# USB_Hub.net
KiCad netlist of a schematic drawn in EAGLE
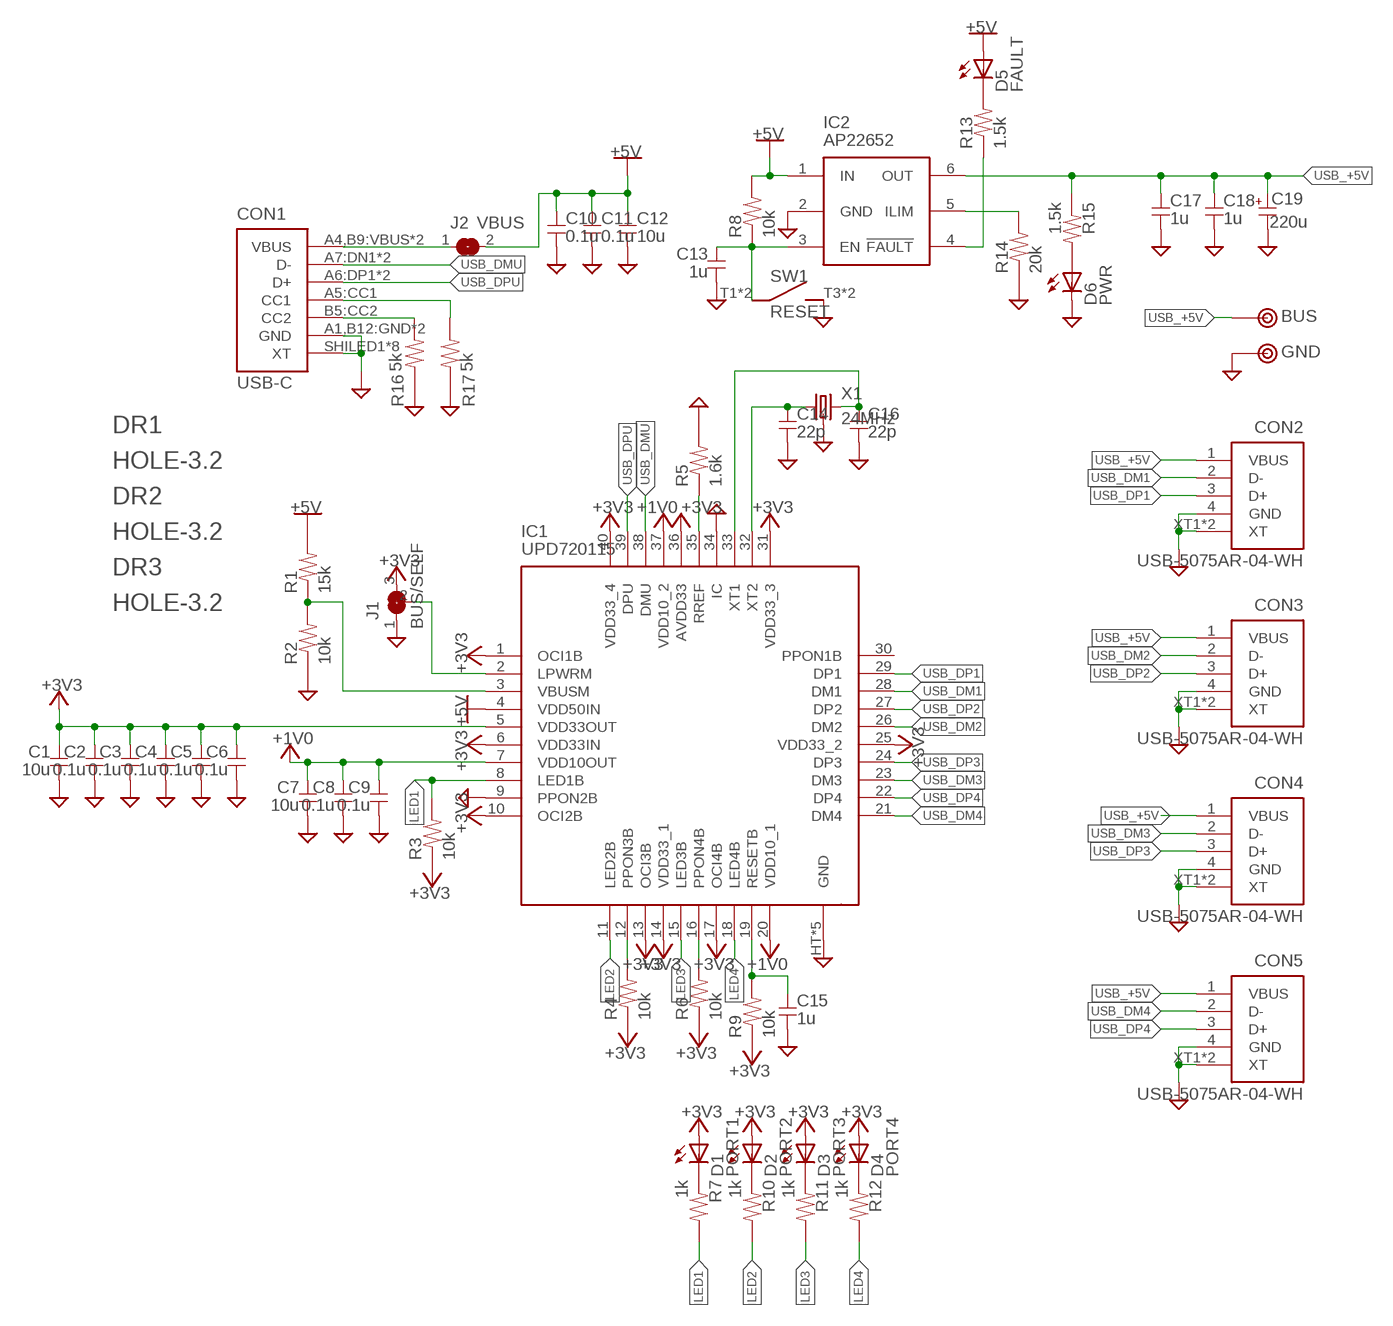
[diagram p0: schematic, sheet 1]

(export (version "E")
  (design (tool "Eeschema 10.0.6"))
  (components
    (comp (ref "C1")
      (value "10u")
      (footprint "eagle-import:1608")
      (libsource (lib "eagle-import") (part "C-1608"))
    )
    (comp (ref "C2")
      (value "0.1u")
      (footprint "eagle-import:1608")
      (libsource (lib "eagle-import") (part "C-1608"))
    )
    (comp (ref "C3")
      (value "0.1u")
      (footprint "eagle-import:1608")
      (libsource (lib "eagle-import") (part "C-1608"))
    )
    (comp (ref "C4")
      (value "0.1u")
      (footprint "eagle-import:1608")
      (libsource (lib "eagle-import") (part "C-1608"))
    )
    (comp (ref "C5")
      (value "0.1u")
      (footprint "eagle-import:1608")
      (libsource (lib "eagle-import") (part "C-1608"))
    )
    (comp (ref "C6")
      (value "0.1u")
      (footprint "eagle-import:1608")
      (libsource (lib "eagle-import") (part "C-1608"))
    )
    (comp (ref "C7")
      (value "10u")
      (footprint "eagle-import:1608")
      (libsource (lib "eagle-import") (part "C-1608"))
    )
    (comp (ref "C8")
      (value "0.1u")
      (footprint "eagle-import:1608")
      (libsource (lib "eagle-import") (part "C-1608"))
    )
    (comp (ref "C9")
      (value "0.1u")
      (footprint "eagle-import:1608")
      (libsource (lib "eagle-import") (part "C-1608"))
    )
    (comp (ref "C10")
      (value "0.1u")
      (footprint "eagle-import:1608")
      (libsource (lib "eagle-import") (part "C-1608"))
    )
    (comp (ref "C11")
      (value "0.1u")
      (footprint "eagle-import:1608")
      (libsource (lib "eagle-import") (part "C-1608"))
    )
    (comp (ref "C12")
      (value "10u")
      (footprint "eagle-import:2012")
      (libsource (lib "eagle-import") (part "C-2012"))
    )
    (comp (ref "C13")
      (value "1u")
      (footprint "eagle-import:1608")
      (libsource (lib "eagle-import") (part "C-1608"))
    )
    (comp (ref "C14")
      (value "22p")
      (footprint "eagle-import:1608")
      (libsource (lib "eagle-import") (part "C-1608"))
    )
    (comp (ref "C15")
      (value "1u")
      (footprint "eagle-import:1608")
      (libsource (lib "eagle-import") (part "C-1608"))
    )
    (comp (ref "C16")
      (value "22p")
      (footprint "eagle-import:1608")
      (libsource (lib "eagle-import") (part "C-1608"))
    )
    (comp (ref "C17")
      (value "1u")
      (footprint "eagle-import:1608")
      (libsource (lib "eagle-import") (part "C-1608"))
    )
    (comp (ref "C18")
      (value "1u")
      (footprint "eagle-import:1608")
      (libsource (lib "eagle-import") (part "C-1608"))
    )
    (comp (ref "C19")
      (value "220u")
      (footprint "eagle-import:E2.5-6.5")
      (libsource (lib "eagle-import") (part "CPOLE2.5-6.5"))
    )
    (comp (ref "CON1")
      (value "USB-C")
      (footprint "eagle-import:5077CR-16-SMC2-BK-TR")
      (libsource (lib "eagle-import") (part "USB-C"))
    )
    (comp (ref "CON2")
      (value "USB-5075AR-04-WH")
      (footprint "eagle-import:5075AR-04-WH")
      (libsource (lib "eagle-import") (part "USB-5075AR-04-WH"))
    )
    (comp (ref "CON3")
      (value "USB-5075AR-04-WH")
      (footprint "eagle-import:5075AR-04-WH")
      (libsource (lib "eagle-import") (part "USB-5075AR-04-WH"))
    )
    (comp (ref "CON4")
      (value "USB-5075AR-04-WH")
      (footprint "eagle-import:5075AR-04-WH")
      (libsource (lib "eagle-import") (part "USB-5075AR-04-WH"))
    )
    (comp (ref "CON5")
      (value "USB-5075AR-04-WH")
      (footprint "eagle-import:5075AR-04-WH")
      (libsource (lib "eagle-import") (part "USB-5075AR-04-WH"))
    )
    (comp (ref "D1")
      (value "PORT1")
      (footprint "eagle-import:LED2.5")
      (libsource (lib "eagle-import") (part "LED-2.5"))
    )
    (comp (ref "D2")
      (value "PORT2")
      (footprint "eagle-import:LED2.5")
      (libsource (lib "eagle-import") (part "LED-2.5"))
    )
    (comp (ref "D3")
      (value "PORT3")
      (footprint "eagle-import:LED2.5")
      (libsource (lib "eagle-import") (part "LED-2.5"))
    )
    (comp (ref "D4")
      (value "PORT4")
      (footprint "eagle-import:LED2.5")
      (libsource (lib "eagle-import") (part "LED-2.5"))
    )
    (comp (ref "D5")
      (value "FAULT")
      (footprint "eagle-import:D1608")
      (libsource (lib "eagle-import") (part "LED-SMD1608"))
    )
    (comp (ref "D6")
      (value "PWR")
      (footprint "eagle-import:D1608")
      (libsource (lib "eagle-import") (part "LED-SMD1608"))
    )
    (comp (ref "DR1")
      (value "HOLE-3.2")
      (footprint "eagle-import:HOLE_3.2")
      (libsource (lib "eagle-import") (part "HOLE-3.2"))
    )
    (comp (ref "DR2")
      (value "HOLE-3.2")
      (footprint "eagle-import:HOLE_3.2")
      (libsource (lib "eagle-import") (part "HOLE-3.2"))
    )
    (comp (ref "DR3")
      (value "HOLE-3.2")
      (footprint "eagle-import:HOLE_3.2")
      (libsource (lib "eagle-import") (part "HOLE-3.2"))
    )
    (comp (ref "IC1")
      (value "UPD720115")
      (footprint "eagle-import:QFN40HT")
      (libsource (lib "eagle-import") (part "UPD720115"))
    )
    (comp (ref "IC2")
      (value "AP22652")
      (footprint "eagle-import:SOT23-6")
      (libsource (lib "eagle-import") (part "AP22652"))
    )
    (comp (ref "J1")
      (value "BUS/SELF")
      (footprint "eagle-import:1608-3-J")
      (libsource (lib "eagle-import") (part "SJ-3-1608"))
    )
    (comp (ref "J2")
      (value "VBUS")
      (footprint "eagle-import:1608-J")
      (libsource (lib "eagle-import") (part "SJ-1608"))
    )
    (comp (ref "R1")
      (value "15k")
      (footprint "eagle-import:1608")
      (libsource (lib "eagle-import") (part "R-1608"))
    )
    (comp (ref "R2")
      (value "10k")
      (footprint "eagle-import:1608")
      (libsource (lib "eagle-import") (part "R-1608"))
    )
    (comp (ref "R3")
      (value "10k")
      (footprint "eagle-import:1608")
      (libsource (lib "eagle-import") (part "R-1608"))
    )
    (comp (ref "R4")
      (value "10k")
      (footprint "eagle-import:1608")
      (libsource (lib "eagle-import") (part "R-1608"))
    )
    (comp (ref "R5")
      (value "1.6k")
      (footprint "eagle-import:1608")
      (libsource (lib "eagle-import") (part "R-1608"))
    )
    (comp (ref "R6")
      (value "10k")
      (footprint "eagle-import:1608")
      (libsource (lib "eagle-import") (part "R-1608"))
    )
    (comp (ref "R7")
      (value "1k")
      (footprint "eagle-import:1608")
      (libsource (lib "eagle-import") (part "R-1608"))
    )
    (comp (ref "R8")
      (value "10k")
      (footprint "eagle-import:1608")
      (libsource (lib "eagle-import") (part "R-1608"))
    )
    (comp (ref "R9")
      (value "10k")
      (footprint "eagle-import:1608")
      (libsource (lib "eagle-import") (part "R-1608"))
    )
    (comp (ref "R10")
      (value "1k")
      (footprint "eagle-import:1608")
      (libsource (lib "eagle-import") (part "R-1608"))
    )
    (comp (ref "R11")
      (value "1k")
      (footprint "eagle-import:1608")
      (libsource (lib "eagle-import") (part "R-1608"))
    )
    (comp (ref "R12")
      (value "1k")
      (footprint "eagle-import:1608")
      (libsource (lib "eagle-import") (part "R-1608"))
    )
    (comp (ref "R13")
      (value "1.5k")
      (footprint "eagle-import:1608")
      (libsource (lib "eagle-import") (part "R-1608"))
    )
    (comp (ref "R14")
      (value "20k")
      (footprint "eagle-import:1608")
      (libsource (lib "eagle-import") (part "R-1608"))
    )
    (comp (ref "R15")
      (value "1.5k")
      (footprint "eagle-import:1608")
      (libsource (lib "eagle-import") (part "R-1608"))
    )
    (comp (ref "R16")
      (value "5k")
      (footprint "eagle-import:1608")
      (libsource (lib "eagle-import") (part "R-1608"))
    )
    (comp (ref "R17")
      (value "5k")
      (footprint "eagle-import:1608")
      (libsource (lib "eagle-import") (part "R-1608"))
    )
    (comp (ref "SW1")
      (value "RESET")
      (footprint "eagle-import:SW_PUSH")
      (libsource (lib "eagle-import") (part "SW"))
    )
    (comp (ref "TP1")
      (value "BUS")
      (footprint "eagle-import:TESTPIN")
      (libsource (lib "eagle-import") (part "TESTPIN"))
    )
    (comp (ref "TP2")
      (value "GND")
      (footprint "eagle-import:TESTPIN")
      (libsource (lib "eagle-import") (part "TESTPIN"))
    )
    (comp (ref "X1")
      (value "24MHz")
      (footprint "eagle-import:KC3225")
      (libsource (lib "eagle-import") (part "CRYSTAL2"))
    )
  )
  (nets
    (net (code "1") (name "+1V0") (class "Default")
      (node (ref "C7") (pin "1") (pinfunction "1_1") (pintype "passive"))
      (node (ref "C8") (pin "1") (pinfunction "1_1") (pintype "passive"))
      (node (ref "C9") (pin "1") (pinfunction "1_1") (pintype "passive"))
      (node (ref "IC1") (pin "20") (pinfunction "VDD10_1_20") (pintype "input"))
      (node (ref "IC1") (pin "37") (pinfunction "VDD10_2_37") (pintype "input"))
      (node (ref "IC1") (pin "7") (pinfunction "VDD10OUT_7") (pintype "output"))
    )
    (net (code "2") (name "+3V3") (class "Default")
      (node (ref "C1") (pin "1") (pinfunction "1_1") (pintype "passive"))
      (node (ref "C2") (pin "1") (pinfunction "1_1") (pintype "passive"))
      (node (ref "C3") (pin "1") (pinfunction "1_1") (pintype "passive"))
      (node (ref "C4") (pin "1") (pinfunction "1_1") (pintype "passive"))
      (node (ref "C5") (pin "1") (pinfunction "1_1") (pintype "passive"))
      (node (ref "C6") (pin "1") (pinfunction "1_1") (pintype "passive"))
      (node (ref "D1") (pin "A") (pinfunction "A_A") (pintype "passive"))
      (node (ref "D2") (pin "A") (pinfunction "A_A") (pintype "passive"))
      (node (ref "D3") (pin "A") (pinfunction "A_A") (pintype "passive"))
      (node (ref "D4") (pin "A") (pinfunction "A_A") (pintype "passive"))
      (node (ref "IC1") (pin "1") (pinfunction "OCI1B_1") (pintype "input"))
      (node (ref "IC1") (pin "10") (pinfunction "OCI2B_10") (pintype "input"))
      (node (ref "IC1") (pin "13") (pinfunction "OCI3B_13") (pintype "input"))
      (node (ref "IC1") (pin "14") (pinfunction "VDD33_1_14") (pintype "input"))
      (node (ref "IC1") (pin "17") (pinfunction "OCI4B_17") (pintype "input"))
      (node (ref "IC1") (pin "25") (pinfunction "VDD33_2_25") (pintype "input"))
      (node (ref "IC1") (pin "31") (pinfunction "VDD33_3_31") (pintype "input"))
      (node (ref "IC1") (pin "36") (pinfunction "AVDD33_36") (pintype "input"))
      (node (ref "IC1") (pin "40") (pinfunction "VDD33_4_40") (pintype "input"))
      (node (ref "IC1") (pin "5") (pinfunction "VDD33OUT_5") (pintype "output"))
      (node (ref "IC1") (pin "6") (pinfunction "VDD33IN_6") (pintype "input"))
      (node (ref "J1") (pin "3") (pinfunction "3_3") (pintype "passive"))
      (node (ref "R3") (pin "1") (pinfunction "1_1") (pintype "passive"))
      (node (ref "R4") (pin "1") (pinfunction "1_1") (pintype "passive"))
      (node (ref "R6") (pin "1") (pinfunction "1_1") (pintype "passive"))
      (node (ref "R9") (pin "1") (pinfunction "1_1") (pintype "passive"))
    )
    (net (code "3") (name "+5V") (class "Default")
      (node (ref "C10") (pin "1") (pinfunction "1_1") (pintype "passive"))
      (node (ref "C11") (pin "1") (pinfunction "1_1") (pintype "passive"))
      (node (ref "C12") (pin "1") (pinfunction "1_1") (pintype "passive"))
      (node (ref "D5") (pin "A") (pinfunction "A_A") (pintype "passive"))
      (node (ref "IC1") (pin "4") (pinfunction "VDD50IN_4") (pintype "input"))
      (node (ref "IC2") (pin "1") (pinfunction "IN_1") (pintype "input"))
      (node (ref "J2") (pin "2") (pinfunction "2_2") (pintype "passive"))
      (node (ref "R1") (pin "2") (pinfunction "2_2") (pintype "passive"))
      (node (ref "R8") (pin "2") (pinfunction "2_2") (pintype "passive"))
    )
    (net (code "4") (name "GND") (class "Default")
      (node (ref "C1") (pin "2") (pinfunction "2_2") (pintype "passive"))
      (node (ref "C10") (pin "2") (pinfunction "2_2") (pintype "passive"))
      (node (ref "C11") (pin "2") (pinfunction "2_2") (pintype "passive"))
      (node (ref "C12") (pin "2") (pinfunction "2_2") (pintype "passive"))
      (node (ref "C13") (pin "2") (pinfunction "2_2") (pintype "passive"))
      (node (ref "C14") (pin "2") (pinfunction "2_2") (pintype "passive"))
      (node (ref "C15") (pin "2") (pinfunction "2_2") (pintype "passive"))
      (node (ref "C16") (pin "2") (pinfunction "2_2") (pintype "passive"))
      (node (ref "C17") (pin "2") (pinfunction "2_2") (pintype "passive"))
      (node (ref "C18") (pin "2") (pinfunction "2_2") (pintype "passive"))
      (node (ref "C19") (pin "-") (pinfunction "2_-") (pintype "passive"))
      (node (ref "C2") (pin "2") (pinfunction "2_2") (pintype "passive"))
      (node (ref "C3") (pin "2") (pinfunction "2_2") (pintype "passive"))
      (node (ref "C4") (pin "2") (pinfunction "2_2") (pintype "passive"))
      (node (ref "C5") (pin "2") (pinfunction "2_2") (pintype "passive"))
      (node (ref "C6") (pin "2") (pinfunction "2_2") (pintype "passive"))
      (node (ref "C7") (pin "2") (pinfunction "2_2") (pintype "passive"))
      (node (ref "C8") (pin "2") (pinfunction "2_2") (pintype "passive"))
      (node (ref "C9") (pin "2") (pinfunction "2_2") (pintype "passive"))
      (node (ref "CON1") (pin "A1,B12:GND") (pinfunction "GND_A1,B12:GND") (pintype "bidirectional"))
      (node (ref "CON1") (pin "B1,A12:GND") (pinfunction "GND_B1,A12:GND") (pintype "bidirectional"))
      (node (ref "CON1") (pin "SHILED1") (pinfunction "XT_SHILED1") (pintype "bidirectional"))
      (node (ref "CON1") (pin "SHILED2") (pinfunction "XT_SHILED2") (pintype "bidirectional"))
      (node (ref "CON1") (pin "SHILED3") (pinfunction "XT_SHILED3") (pintype "bidirectional"))
      (node (ref "CON1") (pin "SHILED4") (pinfunction "XT_SHILED4") (pintype "bidirectional"))
      (node (ref "CON1") (pin "SHILED5") (pinfunction "XT_SHILED5") (pintype "bidirectional"))
      (node (ref "CON1") (pin "SHILED6") (pinfunction "XT_SHILED6") (pintype "bidirectional"))
      (node (ref "CON1") (pin "SHILED7") (pinfunction "XT_SHILED7") (pintype "bidirectional"))
      (node (ref "CON1") (pin "SHILED8") (pinfunction "XT_SHILED8") (pintype "bidirectional"))
      (node (ref "CON2") (pin "4") (pinfunction "GND_4") (pintype "bidirectional"))
      (node (ref "CON2") (pin "XT1") (pinfunction "XT_XT1") (pintype "bidirectional"))
      (node (ref "CON2") (pin "XT2") (pinfunction "XT_XT2") (pintype "bidirectional"))
      (node (ref "CON3") (pin "4") (pinfunction "GND_4") (pintype "bidirectional"))
      (node (ref "CON3") (pin "XT1") (pinfunction "XT_XT1") (pintype "bidirectional"))
      (node (ref "CON3") (pin "XT2") (pinfunction "XT_XT2") (pintype "bidirectional"))
      (node (ref "CON4") (pin "4") (pinfunction "GND_4") (pintype "bidirectional"))
      (node (ref "CON4") (pin "XT1") (pinfunction "XT_XT1") (pintype "bidirectional"))
      (node (ref "CON4") (pin "XT2") (pinfunction "XT_XT2") (pintype "bidirectional"))
      (node (ref "CON5") (pin "4") (pinfunction "GND_4") (pintype "bidirectional"))
      (node (ref "CON5") (pin "XT1") (pinfunction "XT_XT1") (pintype "bidirectional"))
      (node (ref "CON5") (pin "XT2") (pinfunction "XT_XT2") (pintype "bidirectional"))
      (node (ref "D6") (pin "K") (pinfunction "K_K") (pintype "passive"))
      (node (ref "IC1") (pin "34") (pinfunction "IC_34") (pintype "input"))
      (node (ref "IC1") (pin "9") (pinfunction "PPON2B_9") (pintype "input"))
      (node (ref "IC1") (pin "HT") (pinfunction "GND_HT") (pintype "input"))
      (node (ref "IC1") (pin "HT1") (pinfunction "GND_HT1") (pintype "input"))
      (node (ref "IC1") (pin "HT2") (pinfunction "GND_HT2") (pintype "input"))
      (node (ref "IC1") (pin "HT3") (pinfunction "GND_HT3") (pintype "input"))
      (node (ref "IC1") (pin "HT4") (pinfunction "GND_HT4") (pintype "input"))
      (node (ref "IC2") (pin "2") (pinfunction "GND_2") (pintype "input"))
      (node (ref "J1") (pin "1") (pinfunction "1_1") (pintype "passive"))
      (node (ref "R14") (pin "1") (pinfunction "1_1") (pintype "passive"))
      (node (ref "R16") (pin "1") (pinfunction "1_1") (pintype "passive"))
      (node (ref "R17") (pin "1") (pinfunction "1_1") (pintype "passive"))
      (node (ref "R2") (pin "1") (pinfunction "1_1") (pintype "passive"))
      (node (ref "R5") (pin "2") (pinfunction "2_2") (pintype "passive"))
      (node (ref "SW1") (pin "T3") (pinfunction "2_T3") (pintype "passive"))
      (node (ref "SW1") (pin "T4") (pinfunction "2_T4") (pintype "passive"))
      (node (ref "TP2") (pin "1") (pinfunction "1_1") (pintype "passive"))
      (node (ref "X1") (pin "2") (pinfunction "GND_2") (pintype "passive"))
      (node (ref "X1") (pin "4") (pinfunction "GND_4") (pintype "passive"))
    )
    (net (code "5") (name "LED1") (class "Default")
      (node (ref "IC1") (pin "8") (pinfunction "LED1B_8") (pintype "bidirectional"))
      (node (ref "R3") (pin "2") (pinfunction "2_2") (pintype "passive"))
      (node (ref "R7") (pin "2") (pinfunction "2_2") (pintype "passive"))
    )
    (net (code "6") (name "LED2") (class "Default")
      (node (ref "IC1") (pin "11") (pinfunction "LED2B_11") (pintype "bidirectional"))
      (node (ref "R10") (pin "2") (pinfunction "2_2") (pintype "passive"))
    )
    (net (code "7") (name "LED3") (class "Default")
      (node (ref "IC1") (pin "15") (pinfunction "LED3B_15") (pintype "bidirectional"))
      (node (ref "R11") (pin "2") (pinfunction "2_2") (pintype "passive"))
    )
    (net (code "8") (name "LED4") (class "Default")
      (node (ref "IC1") (pin "18") (pinfunction "LED4B_18") (pintype "bidirectional"))
      (node (ref "R12") (pin "2") (pinfunction "2_2") (pintype "passive"))
    )
    (net (code "9") (name "Net-(CON1-CC1)") (class "Default")
      (node (ref "CON1") (pin "A5:CC1") (pinfunction "CC1_A5:CC1") (pintype "bidirectional"))
      (node (ref "R17") (pin "2") (pinfunction "2_2") (pintype "passive"))
    )
    (net (code "10") (name "Net-(CON1-CC2)") (class "Default")
      (node (ref "CON1") (pin "B5:CC2") (pinfunction "CC2_B5:CC2") (pintype "bidirectional"))
      (node (ref "R16") (pin "2") (pinfunction "2_2") (pintype "passive"))
    )
    (net (code "11") (name "Net-(CON1-VBUS-PadA4,B9:VBUS)") (class "Default")
      (node (ref "CON1") (pin "A4,B9:VBUS") (pinfunction "VBUS_A4,B9:VBUS") (pintype "output"))
      (node (ref "CON1") (pin "B4,A9:VBUS") (pinfunction "VBUS_B4,A9:VBUS") (pintype "output"))
      (node (ref "J2") (pin "1") (pinfunction "1_1") (pintype "passive"))
    )
    (net (code "12") (name "Net-(D1-PadK)") (class "Default")
      (node (ref "D1") (pin "K") (pinfunction "K_K") (pintype "passive"))
      (node (ref "R7") (pin "1") (pinfunction "1_1") (pintype "passive"))
    )
    (net (code "13") (name "Net-(D2-PadK)") (class "Default")
      (node (ref "D2") (pin "K") (pinfunction "K_K") (pintype "passive"))
      (node (ref "R10") (pin "1") (pinfunction "1_1") (pintype "passive"))
    )
    (net (code "14") (name "Net-(D3-PadK)") (class "Default")
      (node (ref "D3") (pin "K") (pinfunction "K_K") (pintype "passive"))
      (node (ref "R11") (pin "1") (pinfunction "1_1") (pintype "passive"))
    )
    (net (code "15") (name "Net-(D4-PadK)") (class "Default")
      (node (ref "D4") (pin "K") (pinfunction "K_K") (pintype "passive"))
      (node (ref "R12") (pin "1") (pinfunction "1_1") (pintype "passive"))
    )
    (net (code "16") (name "Net-(D5-PadK)") (class "Default")
      (node (ref "D5") (pin "K") (pinfunction "K_K") (pintype "passive"))
      (node (ref "R13") (pin "2") (pinfunction "2_2") (pintype "passive"))
    )
    (net (code "17") (name "Net-(D6-PadA)") (class "Default")
      (node (ref "D6") (pin "A") (pinfunction "A_A") (pintype "passive"))
      (node (ref "R15") (pin "2") (pinfunction "2_2") (pintype "passive"))
    )
    (net (code "18") (name "Net-(IC1-LPWRM)") (class "Default")
      (node (ref "IC1") (pin "2") (pinfunction "LPWRM_2") (pintype "input"))
      (node (ref "J1") (pin "2") (pinfunction "2_2") (pintype "passive"))
    )
    (net (code "19") (name "Net-(IC1-PPON3B)") (class "Default")
      (node (ref "IC1") (pin "12") (pinfunction "PPON3B_12") (pintype "input"))
      (node (ref "R4") (pin "2") (pinfunction "2_2") (pintype "passive"))
    )
    (net (code "20") (name "Net-(IC1-PPON4B)") (class "Default")
      (node (ref "IC1") (pin "16") (pinfunction "PPON4B_16") (pintype "input"))
      (node (ref "R6") (pin "2") (pinfunction "2_2") (pintype "passive"))
    )
    (net (code "21") (name "Net-(IC1-RESETB)") (class "Default")
      (node (ref "C15") (pin "1") (pinfunction "1_1") (pintype "passive"))
      (node (ref "IC1") (pin "19") (pinfunction "RESETB_19") (pintype "input"))
      (node (ref "R9") (pin "2") (pinfunction "2_2") (pintype "passive"))
    )
    (net (code "22") (name "Net-(IC1-RREF)") (class "Default")
      (node (ref "IC1") (pin "35") (pinfunction "RREF_35") (pintype "passive"))
      (node (ref "R5") (pin "1") (pinfunction "1_1") (pintype "passive"))
    )
    (net (code "23") (name "Net-(IC1-VBUSM)") (class "Default")
      (node (ref "IC1") (pin "3") (pinfunction "VBUSM_3") (pintype "input"))
      (node (ref "R1") (pin "1") (pinfunction "1_1") (pintype "passive"))
      (node (ref "R2") (pin "2") (pinfunction "2_2") (pintype "passive"))
    )
    (net (code "24") (name "Net-(IC1-XT1)") (class "Default")
      (node (ref "C16") (pin "1") (pinfunction "1_1") (pintype "passive"))
      (node (ref "IC1") (pin "33") (pinfunction "XT1_33") (pintype "bidirectional"))
      (node (ref "X1") (pin "3") (pinfunction "2_3") (pintype "passive"))
    )
    (net (code "25") (name "Net-(IC1-XT2)") (class "Default")
      (node (ref "C14") (pin "1") (pinfunction "1_1") (pintype "passive"))
      (node (ref "IC1") (pin "32") (pinfunction "XT2_32") (pintype "bidirectional"))
      (node (ref "X1") (pin "1") (pinfunction "1_1") (pintype "passive"))
    )
    (net (code "26") (name "Net-(IC2-EN)") (class "Default")
      (node (ref "C13") (pin "1") (pinfunction "1_1") (pintype "passive"))
      (node (ref "IC2") (pin "3") (pinfunction "EN_3") (pintype "input"))
      (node (ref "R8") (pin "1") (pinfunction "1_1") (pintype "passive"))
      (node (ref "SW1") (pin "T1") (pinfunction "1_T1") (pintype "passive"))
      (node (ref "SW1") (pin "T2") (pinfunction "1_T2") (pintype "passive"))
    )
    (net (code "27") (name "Net-(IC2-ILIM)") (class "Default")
      (node (ref "IC2") (pin "5") (pinfunction "ILIM_5") (pintype "passive"))
      (node (ref "R14") (pin "2") (pinfunction "2_2") (pintype "passive"))
    )
    (net (code "28") (name "Net-(IC2-~{FAULT})") (class "Default")
      (node (ref "IC2") (pin "4") (pinfunction "~{FAULT}_4") (pintype "bidirectional"))
      (node (ref "R13") (pin "1") (pinfunction "1_1") (pintype "passive"))
    )
    (net (code "29") (name "USB_+5V") (class "Default")
      (node (ref "C17") (pin "1") (pinfunction "1_1") (pintype "passive"))
      (node (ref "C18") (pin "1") (pinfunction "1_1") (pintype "passive"))
      (node (ref "C19") (pin "+") (pinfunction "1_+") (pintype "passive"))
      (node (ref "CON2") (pin "1") (pinfunction "VBUS_1") (pintype "output"))
      (node (ref "CON3") (pin "1") (pinfunction "VBUS_1") (pintype "output"))
      (node (ref "CON4") (pin "1") (pinfunction "VBUS_1") (pintype "output"))
      (node (ref "CON5") (pin "1") (pinfunction "VBUS_1") (pintype "output"))
      (node (ref "IC2") (pin "6") (pinfunction "OUT_6") (pintype "output"))
      (node (ref "R15") (pin "1") (pinfunction "1_1") (pintype "passive"))
      (node (ref "TP1") (pin "1") (pinfunction "1_1") (pintype "passive"))
    )
    (net (code "30") (name "USB_DM1") (class "Default")
      (node (ref "CON2") (pin "2") (pinfunction "D-_2") (pintype "bidirectional"))
      (node (ref "IC1") (pin "28") (pinfunction "DM1_28") (pintype "bidirectional"))
    )
    (net (code "31") (name "USB_DM2") (class "Default")
      (node (ref "CON3") (pin "2") (pinfunction "D-_2") (pintype "bidirectional"))
      (node (ref "IC1") (pin "26") (pinfunction "DM2_26") (pintype "bidirectional"))
    )
    (net (code "32") (name "USB_DM3") (class "Default")
      (node (ref "CON4") (pin "2") (pinfunction "D-_2") (pintype "bidirectional"))
      (node (ref "IC1") (pin "23") (pinfunction "DM3_23") (pintype "bidirectional"))
    )
    (net (code "33") (name "USB_DM4") (class "Default")
      (node (ref "CON5") (pin "2") (pinfunction "D-_2") (pintype "bidirectional"))
      (node (ref "IC1") (pin "21") (pinfunction "DM4_21") (pintype "bidirectional"))
    )
    (net (code "34") (name "USB_DMU") (class "Default")
      (node (ref "CON1") (pin "A7:DN1") (pinfunction "D-_A7:DN1") (pintype "bidirectional"))
      (node (ref "CON1") (pin "B7:DN2") (pinfunction "D-_B7:DN2") (pintype "bidirectional"))
      (node (ref "IC1") (pin "38") (pinfunction "DMU_38") (pintype "bidirectional"))
    )
    (net (code "35") (name "USB_DP1") (class "Default")
      (node (ref "CON2") (pin "3") (pinfunction "D+_3") (pintype "bidirectional"))
      (node (ref "IC1") (pin "29") (pinfunction "DP1_29") (pintype "bidirectional"))
    )
    (net (code "36") (name "USB_DP2") (class "Default")
      (node (ref "CON3") (pin "3") (pinfunction "D+_3") (pintype "bidirectional"))
      (node (ref "IC1") (pin "27") (pinfunction "DP2_27") (pintype "bidirectional"))
    )
    (net (code "37") (name "USB_DP3") (class "Default")
      (node (ref "CON4") (pin "3") (pinfunction "D+_3") (pintype "bidirectional"))
      (node (ref "IC1") (pin "24") (pinfunction "DP3_24") (pintype "bidirectional"))
    )
    (net (code "38") (name "USB_DP4") (class "Default")
      (node (ref "CON5") (pin "3") (pinfunction "D+_3") (pintype "bidirectional"))
      (node (ref "IC1") (pin "22") (pinfunction "DP4_22") (pintype "bidirectional"))
    )
    (net (code "39") (name "USB_DPU") (class "Default")
      (node (ref "CON1") (pin "A6:DP1") (pinfunction "D+_A6:DP1") (pintype "bidirectional"))
      (node (ref "CON1") (pin "B6:DP2") (pinfunction "D+_B6:DP2") (pintype "bidirectional"))
      (node (ref "IC1") (pin "39") (pinfunction "DPU_39") (pintype "bidirectional"))
    )
    (net (code "40") (name "unconnected-(IC1-PPON1B-Pad30)") (class "Default")
      (node (ref "IC1") (pin "30") (pinfunction "PPON1B_30") (pintype "bidirectional"))
    )
  )
)
